# Communication-Shield.net
KiCad netlist of a schematic drawn in Altium Designer
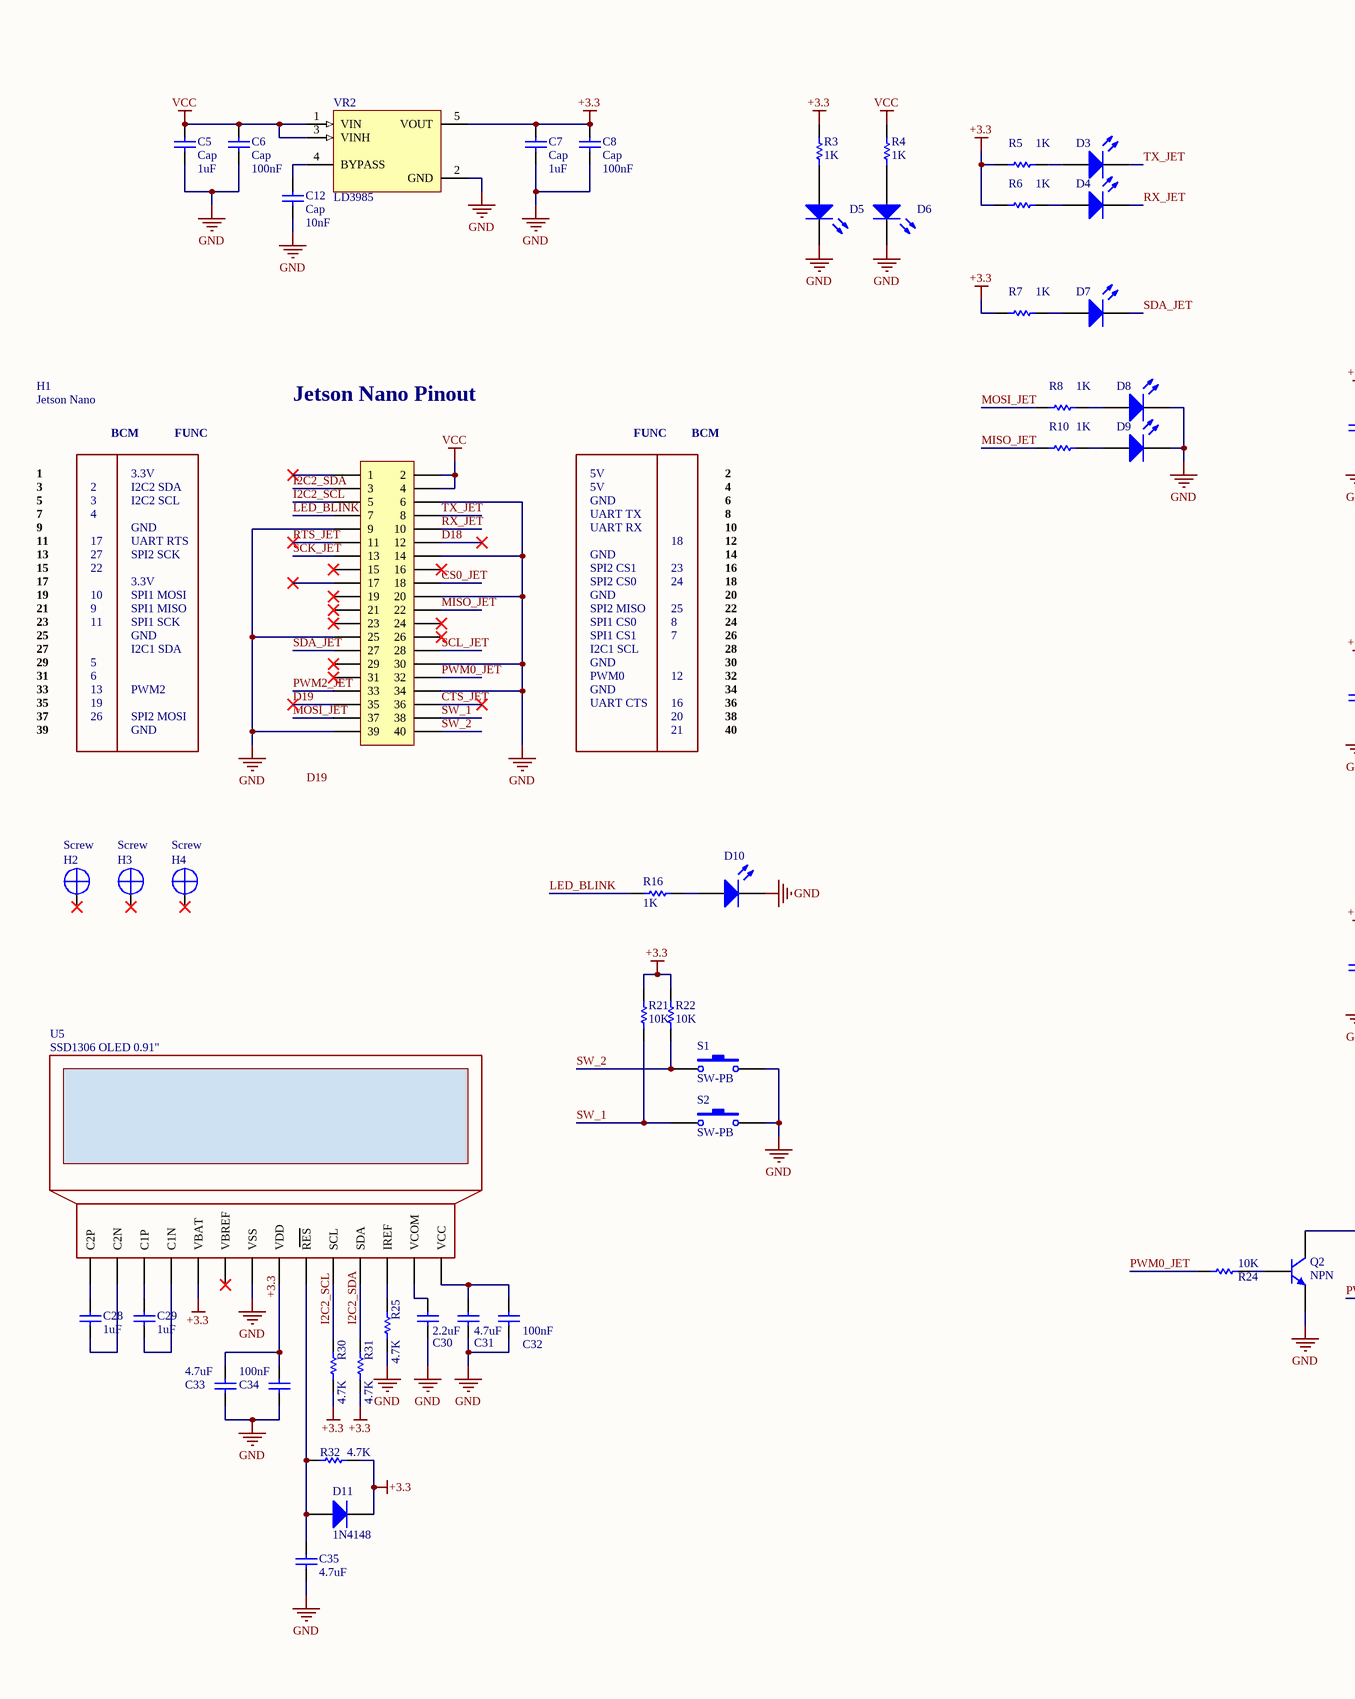
[diagram p0: Communication-Shield.SchDoc, left]
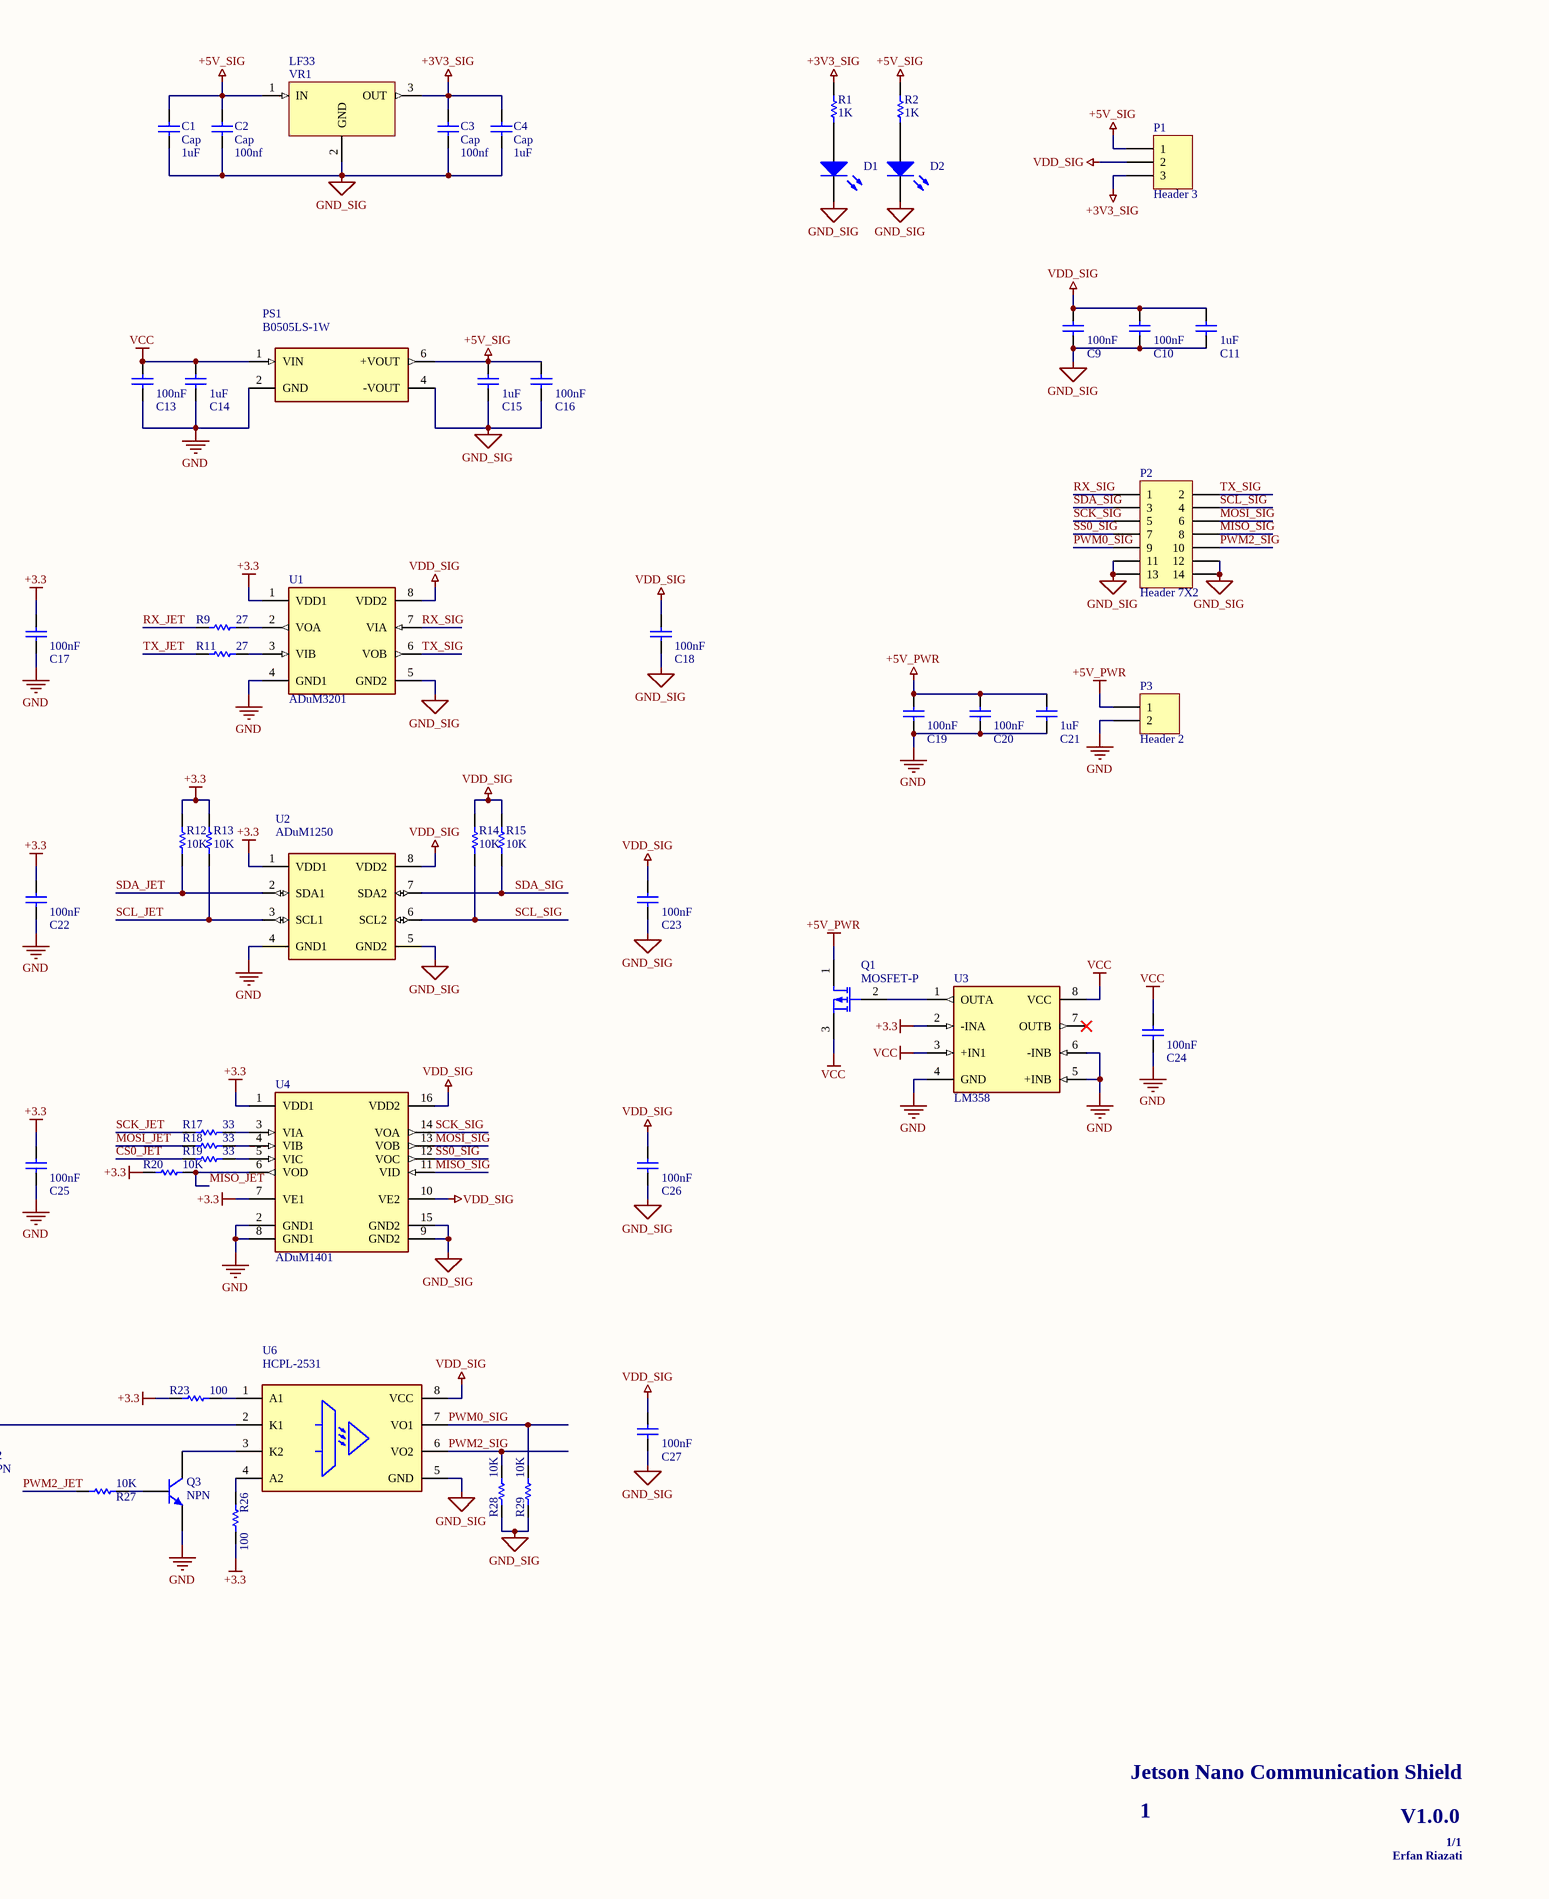
[diagram p1: Communication-Shield.SchDoc, right]

(export (version "E")
  (design (tool "Eeschema 10.0.6"))
  (components
    (comp (ref "C1")
      (value "Cap")
      (footprint "vertigo:C0603")
      (description "Capacitor")
      (fields (field (name "ALTIUM_VALUE") "1uF"))
      (libsource (lib "Miscellaneous Devices") (part "Cap"))
    )
    (comp (ref "C2")
      (value "Cap")
      (footprint "vertigo:C0603")
      (description "Capacitor")
      (fields (field (name "ALTIUM_VALUE") "100nf"))
      (libsource (lib "Miscellaneous Devices") (part "Cap"))
    )
    (comp (ref "C3")
      (value "Cap")
      (footprint "vertigo:C0603")
      (description "Capacitor")
      (fields (field (name "ALTIUM_VALUE") "100nf"))
      (libsource (lib "Miscellaneous Devices") (part "Cap"))
    )
    (comp (ref "C4")
      (value "Cap")
      (footprint "vertigo:C0603")
      (description "Capacitor")
      (fields (field (name "ALTIUM_VALUE") "1uF"))
      (libsource (lib "Miscellaneous Devices") (part "Cap"))
    )
    (comp (ref "C5")
      (value "Cap")
      (footprint "vertigo:C0603")
      (description "Capacitor")
      (fields (field (name "ALTIUM_VALUE") "1uF"))
      (libsource (lib "Miscellaneous Devices") (part "Cap"))
    )
    (comp (ref "C6")
      (value "Cap")
      (footprint "vertigo:C0603")
      (description "Capacitor")
      (fields (field (name "ALTIUM_VALUE") "100nF"))
      (libsource (lib "Miscellaneous Devices") (part "Cap"))
    )
    (comp (ref "C7")
      (value "Cap")
      (footprint "vertigo:C0603")
      (description "Capacitor")
      (fields (field (name "ALTIUM_VALUE") "1uF"))
      (libsource (lib "Miscellaneous Devices") (part "Cap"))
    )
    (comp (ref "C8")
      (value "Cap")
      (footprint "vertigo:C0603")
      (description "Capacitor")
      (fields (field (name "ALTIUM_VALUE") "100nF"))
      (libsource (lib "Miscellaneous Devices") (part "Cap"))
    )
    (comp (ref "C9")
      (value "100nF")
      (footprint "vertigo:C0603")
      (description "Capacitor")
      (fields (field (name "Comment") "Cap"))
      (libsource (lib "Miscellaneous Devices") (part "Cap"))
    )
    (comp (ref "C10")
      (value "100nF")
      (footprint "vertigo:C0603")
      (description "Capacitor")
      (fields (field (name "Comment") "Cap"))
      (libsource (lib "Miscellaneous Devices") (part "Cap"))
    )
    (comp (ref "C11")
      (value "1uF")
      (footprint "vertigo:C0603")
      (description "Capacitor")
      (fields (field (name "Comment") "Cap"))
      (libsource (lib "Miscellaneous Devices") (part "Cap"))
    )
    (comp (ref "C12")
      (value "Cap")
      (footprint "vertigo:C0603")
      (description "Capacitor")
      (fields (field (name "ALTIUM_VALUE") "10nF"))
      (libsource (lib "Miscellaneous Devices") (part "Cap"))
    )
    (comp (ref "C13")
      (value "100nF")
      (footprint "vertigo:C0603")
      (description "Capacitor")
      (fields (field (name "Comment") "Cap"))
      (libsource (lib "Miscellaneous Devices") (part "Cap"))
    )
    (comp (ref "C14")
      (value "1uF")
      (footprint "vertigo:C0603")
      (description "Capacitor")
      (fields (field (name "Comment") "Cap"))
      (libsource (lib "Miscellaneous Devices") (part "Cap"))
    )
    (comp (ref "C15")
      (value "1uF")
      (footprint "vertigo:C0603")
      (description "Capacitor")
      (fields (field (name "Comment") "Cap"))
      (libsource (lib "Miscellaneous Devices") (part "Cap"))
    )
    (comp (ref "C16")
      (value "100nF")
      (footprint "vertigo:C0603")
      (description "Capacitor")
      (fields (field (name "Comment") "Cap"))
      (libsource (lib "Miscellaneous Devices") (part "Cap"))
    )
    (comp (ref "C17")
      (value "100nF")
      (footprint "vertigo:C0603")
      (description "Capacitor")
      (fields (field (name "Comment") "Cap"))
      (libsource (lib "Miscellaneous Devices") (part "Cap"))
    )
    (comp (ref "C18")
      (value "100nF")
      (footprint "vertigo:C0603")
      (description "Capacitor")
      (fields (field (name "Comment") "Cap"))
      (libsource (lib "Miscellaneous Devices") (part "Cap"))
    )
    (comp (ref "C19")
      (value "100nF")
      (footprint "vertigo:C0603")
      (description "Capacitor")
      (fields (field (name "Comment") "Cap"))
      (libsource (lib "Miscellaneous Devices") (part "Cap"))
    )
    (comp (ref "C20")
      (value "100nF")
      (footprint "vertigo:C0603")
      (description "Capacitor")
      (fields (field (name "Comment") "Cap"))
      (libsource (lib "Miscellaneous Devices") (part "Cap"))
    )
    (comp (ref "C21")
      (value "1uF")
      (footprint "vertigo:C0603")
      (description "Capacitor")
      (fields (field (name "Comment") "Cap"))
      (libsource (lib "Miscellaneous Devices") (part "Cap"))
    )
    (comp (ref "C22")
      (value "100nF")
      (footprint "vertigo:C0603")
      (description "Capacitor")
      (fields (field (name "Comment") "Cap"))
      (libsource (lib "Miscellaneous Devices") (part "Cap"))
    )
    (comp (ref "C23")
      (value "100nF")
      (footprint "vertigo:C0603")
      (description "Capacitor")
      (fields (field (name "Comment") "Cap"))
      (libsource (lib "Miscellaneous Devices") (part "Cap"))
    )
    (comp (ref "C24")
      (value "100nF")
      (footprint "vertigo:C0603")
      (description "Capacitor")
      (fields (field (name "Comment") "Cap"))
      (libsource (lib "Miscellaneous Devices") (part "Cap"))
    )
    (comp (ref "C25")
      (value "100nF")
      (footprint "vertigo:C0603")
      (description "Capacitor")
      (fields (field (name "Comment") "Cap"))
      (libsource (lib "Miscellaneous Devices") (part "Cap"))
    )
    (comp (ref "C26")
      (value "100nF")
      (footprint "vertigo:C0603")
      (description "Capacitor")
      (fields (field (name "Comment") "Cap"))
      (libsource (lib "Miscellaneous Devices") (part "Cap"))
    )
    (comp (ref "C27")
      (value "100nF")
      (footprint "vertigo:C0603")
      (description "Capacitor")
      (fields (field (name "Comment") "Cap"))
      (libsource (lib "Miscellaneous Devices") (part "Cap"))
    )
    (comp (ref "C28")
      (value "1uF")
      (footprint "vertigo:C0603")
      (description "Capacitor")
      (fields (field (name "Comment") "Cap"))
      (libsource (lib "Miscellaneous Devices") (part "Cap"))
    )
    (comp (ref "C29")
      (value "1uF")
      (footprint "vertigo:C0603")
      (description "Capacitor")
      (fields (field (name "Comment") "Cap"))
      (libsource (lib "Miscellaneous Devices") (part "Cap"))
    )
    (comp (ref "C30")
      (value "2.2uF")
      (footprint "vertigo:C0603")
      (description "Capacitor")
      (fields (field (name "Comment") "Cap"))
      (libsource (lib "Miscellaneous Devices") (part "Cap"))
    )
    (comp (ref "C31")
      (value "4.7uF")
      (footprint "vertigo:C0603")
      (description "Capacitor")
      (fields (field (name "Comment") "Cap"))
      (libsource (lib "Miscellaneous Devices") (part "Cap"))
    )
    (comp (ref "C32")
      (value "100nF")
      (footprint "vertigo:C0603")
      (description "Capacitor")
      (fields (field (name "Comment") "Cap"))
      (libsource (lib "Miscellaneous Devices") (part "Cap"))
    )
    (comp (ref "C33")
      (value "4.7uF")
      (footprint "vertigo:C0603")
      (description "Capacitor")
      (fields (field (name "Comment") "Cap"))
      (libsource (lib "Miscellaneous Devices") (part "Cap"))
    )
    (comp (ref "C34")
      (value "100nF")
      (footprint "vertigo:C0603")
      (description "Capacitor")
      (fields (field (name "Comment") "Cap"))
      (libsource (lib "Miscellaneous Devices") (part "Cap"))
    )
    (comp (ref "C35")
      (value "4.7uF")
      (footprint "vertigo:C0603")
      (description "Capacitor")
      (fields (field (name "Comment") "Cap"))
      (libsource (lib "Miscellaneous Devices") (part "Cap"))
    )
    (comp (ref "D1")
      (value "Orange")
      (footprint "vertigo:LED-0805 Green")
      (description "Typical RED, GREEN, YELLOW, AMBER GaAs LED")
      (libsource (lib "Miscellaneous Devices") (part "LED2"))
    )
    (comp (ref "D2")
      (value "Orange")
      (footprint "vertigo:LED-0805 Green")
      (description "Typical RED, GREEN, YELLOW, AMBER GaAs LED")
      (libsource (lib "Miscellaneous Devices") (part "LED2"))
    )
    (comp (ref "D3")
      (value "Orange")
      (footprint "vertigo:LED-0805 Orange")
      (description "Typical RED, GREEN, YELLOW, AMBER GaAs LED")
      (libsource (lib "Miscellaneous Devices") (part "LED2"))
    )
    (comp (ref "D4")
      (value "Orange")
      (footprint "vertigo:LED-0805 Orange")
      (description "Typical RED, GREEN, YELLOW, AMBER GaAs LED")
      (libsource (lib "Miscellaneous Devices") (part "LED2"))
    )
    (comp (ref "D5")
      (value "Orange")
      (footprint "vertigo:LED-0805 Green")
      (description "Typical RED, GREEN, YELLOW, AMBER GaAs LED")
      (libsource (lib "Miscellaneous Devices") (part "LED2"))
    )
    (comp (ref "D6")
      (value "Orange")
      (footprint "vertigo:LED-0805 Green")
      (description "Typical RED, GREEN, YELLOW, AMBER GaAs LED")
      (libsource (lib "Miscellaneous Devices") (part "LED2"))
    )
    (comp (ref "D7")
      (value "Orange")
      (footprint "vertigo:LED-0805 Orange")
      (description "Typical RED, GREEN, YELLOW, AMBER GaAs LED")
      (libsource (lib "Miscellaneous Devices") (part "LED2"))
    )
    (comp (ref "D8")
      (value "Orange")
      (footprint "vertigo:LED-0805 Orange")
      (description "Typical RED, GREEN, YELLOW, AMBER GaAs LED")
      (libsource (lib "Miscellaneous Devices") (part "LED2"))
    )
    (comp (ref "D9")
      (value "Orange")
      (footprint "vertigo:LED-0805 Orange")
      (description "Typical RED, GREEN, YELLOW, AMBER GaAs LED")
      (libsource (lib "Miscellaneous Devices") (part "LED2"))
    )
    (comp (ref "D10")
      (value "Orange")
      (footprint "vertigo:LED-0805 Orange")
      (description "Typical RED, GREEN, YELLOW, AMBER GaAs LED")
      (libsource (lib "Miscellaneous Devices") (part "LED2"))
    )
    (comp (ref "D11")
      (value "1N4148")
      (footprint "vertigo:SOD-323 Diode")
      (description "Default Diode")
      (libsource (lib "Miscellaneous Devices") (part "Diode"))
    )
    (comp (ref "H1")
      (value "Jetson Nano")
      (footprint "vertigo:Jetson Nano Header 40-Pin")
      (libsource (lib "vertigo") (part "Jetson Nano"))
    )
    (comp (ref "H2")
      (value "Screw")
      (footprint "vertigo:3mm Screw Hole - 2")
      (description "PCB MOUNTING SCREW")
      (libsource (lib "vertigo") (part "Screw"))
    )
    (comp (ref "H3")
      (value "Screw")
      (footprint "vertigo:3mm Screw Hole - 2")
      (description "PCB MOUNTING SCREW")
      (libsource (lib "vertigo") (part "Screw"))
    )
    (comp (ref "H4")
      (value "Screw")
      (footprint "vertigo:3mm Screw Hole - 2")
      (description "PCB MOUNTING SCREW")
      (libsource (lib "vertigo") (part "Screw"))
    )
    (comp (ref "P1")
      (value "Header 3")
      (footprint "vertigo:Jumper Selector")
      (description "Header, 3-Pin")
      (libsource (lib "Miscellaneous Connectors") (part "Header 3"))
    )
    (comp (ref "P2")
      (value "Header 7X2")
      (footprint "vertigo:IDC 14-Pin 2x7")
      (description "Header, 7-Pin, Dual row")
      (libsource (lib "Miscellaneous Connectors") (part "Header 7X2"))
    )
    (comp (ref "P3")
      (value "Header 2")
      (footprint "vertigo:XH Connector 2-Pin")
      (description "Header, 2-Pin")
      (libsource (lib "Miscellaneous Connectors") (part "Header 2"))
    )
    (comp (ref "PS1")
      (value "B0505LS-1W")
      (footprint "vertigo:B0505LS-1W")
      (description "Compact, isolated DC-DC Converter module")
      (libsource (lib "vertigo") (part "B0505LS-1W"))
    )
    (comp (ref "Q1")
      (value "MOSFET-P")
      (footprint "vertigo:SOT-23")
      (description "P-Channel MOSFET")
      (libsource (lib "Miscellaneous Devices") (part "MOSFET-P"))
    )
    (comp (ref "Q2")
      (value "NPN")
      (footprint "vertigo:SOT-23")
      (description "NPN Bipolar Transistor")
      (libsource (lib "Miscellaneous Devices") (part "NPN"))
    )
    (comp (ref "Q3")
      (value "NPN")
      (footprint "vertigo:SOT-23")
      (description "NPN Bipolar Transistor")
      (libsource (lib "Miscellaneous Devices") (part "NPN"))
    )
    (comp (ref "R1")
      (value "1K")
      (footprint "vertigo:R0603")
      (description "Resistor")
      (fields (field (name "Comment") "Res1"))
      (libsource (lib "Miscellaneous Devices") (part "Res1"))
    )
    (comp (ref "R2")
      (value "1K")
      (footprint "vertigo:R0603")
      (description "Resistor")
      (fields (field (name "Comment") "Res1"))
      (libsource (lib "Miscellaneous Devices") (part "Res1"))
    )
    (comp (ref "R3")
      (value "1K")
      (footprint "vertigo:R0603")
      (description "Resistor")
      (fields (field (name "Comment") "Res1"))
      (libsource (lib "Miscellaneous Devices") (part "Res1"))
    )
    (comp (ref "R4")
      (value "1K")
      (footprint "vertigo:R0603")
      (description "Resistor")
      (fields (field (name "Comment") "Res1"))
      (libsource (lib "Miscellaneous Devices") (part "Res1"))
    )
    (comp (ref "R5")
      (value "1K")
      (footprint "vertigo:R0603")
      (description "Resistor")
      (fields (field (name "Comment") "Res1"))
      (libsource (lib "Miscellaneous Devices") (part "Res1"))
    )
    (comp (ref "R6")
      (value "1K")
      (footprint "vertigo:R0603")
      (description "Resistor")
      (fields (field (name "Comment") "Res1"))
      (libsource (lib "Miscellaneous Devices") (part "Res1"))
    )
    (comp (ref "R7")
      (value "1K")
      (footprint "vertigo:R0603")
      (description "Resistor")
      (fields (field (name "Comment") "Res1"))
      (libsource (lib "Miscellaneous Devices") (part "Res1"))
    )
    (comp (ref "R8")
      (value "1K")
      (footprint "vertigo:R0603")
      (description "Resistor")
      (fields (field (name "Comment") "Res1"))
      (libsource (lib "Miscellaneous Devices") (part "Res1"))
    )
    (comp (ref "R9")
      (value "27")
      (footprint "vertigo:R0603")
      (description "Resistor")
      (fields (field (name "Comment") "Res1"))
      (libsource (lib "Miscellaneous Devices") (part "Res1"))
    )
    (comp (ref "R10")
      (value "1K")
      (footprint "vertigo:R0603")
      (description "Resistor")
      (fields (field (name "Comment") "Res1"))
      (libsource (lib "Miscellaneous Devices") (part "Res1"))
    )
    (comp (ref "R11")
      (value "27")
      (footprint "vertigo:R0603")
      (description "Resistor")
      (fields (field (name "Comment") "Res1"))
      (libsource (lib "Miscellaneous Devices") (part "Res1"))
    )
    (comp (ref "R12")
      (value "10K")
      (footprint "vertigo:R0603")
      (description "Resistor")
      (fields (field (name "Comment") "Res1"))
      (libsource (lib "Miscellaneous Devices") (part "Res1"))
    )
    (comp (ref "R13")
      (value "10K")
      (footprint "vertigo:R0603")
      (description "Resistor")
      (fields (field (name "Comment") "Res1"))
      (libsource (lib "Miscellaneous Devices") (part "Res1"))
    )
    (comp (ref "R14")
      (value "10K")
      (footprint "vertigo:R0603")
      (description "Resistor")
      (fields (field (name "Comment") "Res1"))
      (libsource (lib "Miscellaneous Devices") (part "Res1"))
    )
    (comp (ref "R15")
      (value "10K")
      (footprint "vertigo:R0603")
      (description "Resistor")
      (fields (field (name "Comment") "Res1"))
      (libsource (lib "Miscellaneous Devices") (part "Res1"))
    )
    (comp (ref "R16")
      (value "1K")
      (footprint "vertigo:R0603")
      (description "Resistor")
      (fields (field (name "Comment") "Res1"))
      (libsource (lib "Miscellaneous Devices") (part "Res1"))
    )
    (comp (ref "R17")
      (value "33")
      (footprint "vertigo:R0603")
      (description "Resistor")
      (fields (field (name "Comment") "Res1"))
      (libsource (lib "Miscellaneous Devices") (part "Res1"))
    )
    (comp (ref "R18")
      (value "33")
      (footprint "vertigo:R0603")
      (description "Resistor")
      (fields (field (name "Comment") "Res1"))
      (libsource (lib "Miscellaneous Devices") (part "Res1"))
    )
    (comp (ref "R19")
      (value "33")
      (footprint "vertigo:R0603")
      (description "Resistor")
      (fields (field (name "Comment") "Res1"))
      (libsource (lib "Miscellaneous Devices") (part "Res1"))
    )
    (comp (ref "R20")
      (value "10K")
      (footprint "vertigo:R0603")
      (description "Resistor")
      (fields (field (name "Comment") "Res1"))
      (libsource (lib "Miscellaneous Devices") (part "Res1"))
    )
    (comp (ref "R21")
      (value "10K")
      (footprint "vertigo:R0603")
      (description "Resistor")
      (fields (field (name "Comment") "Res1"))
      (libsource (lib "Miscellaneous Devices") (part "Res1"))
    )
    (comp (ref "R22")
      (value "10K")
      (footprint "vertigo:R0603")
      (description "Resistor")
      (fields (field (name "Comment") "Res1"))
      (libsource (lib "Miscellaneous Devices") (part "Res1"))
    )
    (comp (ref "R23")
      (value "100")
      (footprint "vertigo:R0603")
      (description "Resistor")
      (fields (field (name "Comment") "Res1"))
      (libsource (lib "Miscellaneous Devices") (part "Res1"))
    )
    (comp (ref "R24")
      (value "10K")
      (footprint "vertigo:R0603")
      (description "Resistor")
      (fields (field (name "Comment") "Res1"))
      (libsource (lib "Miscellaneous Devices") (part "Res1"))
    )
    (comp (ref "R25")
      (value "4.7K")
      (footprint "vertigo:R0603")
      (description "Resistor")
      (fields (field (name "Comment") "Res1"))
      (libsource (lib "Miscellaneous Devices") (part "Res1"))
    )
    (comp (ref "R26")
      (value "100")
      (footprint "vertigo:R0603")
      (description "Resistor")
      (fields (field (name "Comment") "Res1"))
      (libsource (lib "Miscellaneous Devices") (part "Res1"))
    )
    (comp (ref "R27")
      (value "10K")
      (footprint "vertigo:R0603")
      (description "Resistor")
      (fields (field (name "Comment") "Res1"))
      (libsource (lib "Miscellaneous Devices") (part "Res1"))
    )
    (comp (ref "R28")
      (value "10K")
      (footprint "vertigo:R0603")
      (description "Resistor")
      (fields (field (name "Comment") "Res1"))
      (libsource (lib "Miscellaneous Devices") (part "Res1"))
    )
    (comp (ref "R29")
      (value "10K")
      (footprint "vertigo:R0603")
      (description "Resistor")
      (fields (field (name "Comment") "Res1"))
      (libsource (lib "Miscellaneous Devices") (part "Res1"))
    )
    (comp (ref "R30")
      (value "4.7K")
      (footprint "vertigo:R0603")
      (description "Resistor")
      (fields (field (name "Comment") "Res1"))
      (libsource (lib "Miscellaneous Devices") (part "Res1"))
    )
    (comp (ref "R31")
      (value "4.7K")
      (footprint "vertigo:R0603")
      (description "Resistor")
      (fields (field (name "Comment") "Res1"))
      (libsource (lib "Miscellaneous Devices") (part "Res1"))
    )
    (comp (ref "R32")
      (value "4.7K")
      (footprint "vertigo:R0603")
      (description "Resistor")
      (fields (field (name "Comment") "Res1"))
      (libsource (lib "Miscellaneous Devices") (part "Res1"))
    )
    (comp (ref "S1")
      (value "SW-PB")
      (footprint "vertigo:Tactile Switch SMD - 2")
      (description "Switch")
      (libsource (lib "Miscellaneous Devices") (part "SW-PB"))
    )
    (comp (ref "S2")
      (value "SW-PB")
      (footprint "vertigo:Tactile Switch SMD - 2")
      (description "Switch")
      (libsource (lib "Miscellaneous Devices") (part "SW-PB"))
    )
    (comp (ref "U1")
      (value "ADuM3201")
      (footprint "vertigo:SOIC-8")
      (description "Dual-Channel, Digital Isolators, Enhanced System-Level ESD Reliability")
      (libsource (lib "vertigo") (part "ADuM3201"))
    )
    (comp (ref "U2")
      (value "ADuM1250")
      (footprint "vertigo:SOIC-8")
      (description "Hot Swappable, Dual I2C Isolators")
      (libsource (lib "vertigo") (part "ADuM1250"))
    )
    (comp (ref "U3")
      (value "LM358")
      (footprint "vertigo:SOIC-8")
      (description "2-Channel, 1MHz, industry standard, 32V Op-Amp")
      (libsource (lib "vertigo") (part "LM358"))
    )
    (comp (ref "U4")
      (value "ADuM1401")
      (footprint "vertigo:SOIC-16")
      (description "Quad-Channel Digital Isolators")
      (libsource (lib "vertigo") (part "ADuM1401"))
    )
    (comp (ref "U5")
      (value "SSD1306 OLED 0.91\"")
      (footprint "vertigo:SSD1306 OLED 0.91\"")
      (libsource (lib "vertigo") (part "SSD1306 OLED 0.91{dblquote}"))
    )
    (comp (ref "U6")
      (value "HCPL-2531")
      (footprint "vertigo:SOIC-8")
      (libsource (lib "vertigo") (part "HCPL-2531"))
    )
    (comp (ref "VR1")
      (value "LF33")
      (footprint "DPAK TO-252")
      (description "Very low drop voltage regulator with inhibit function")
      (libsource (lib "vertigo") (part "LF33"))
    )
    (comp (ref "VR2")
      (value "LD3985")
      (footprint "SOT23-5")
      (description "Ultra low drop and low noise BiCMOS voltage regulators")
      (libsource (lib "vertigo") (part "LD3985"))
    )
  )
  (nets
    (net (code "1") (name "+3.3") (class "Default")
      (node (ref "C17") (pin "1") (pinfunction "1_1") (pintype "passive"))
      (node (ref "C22") (pin "1") (pinfunction "1_1") (pintype "passive"))
      (node (ref "C25") (pin "1") (pinfunction "1_1") (pintype "passive"))
      (node (ref "C33") (pin "1") (pinfunction "1_1") (pintype "passive"))
      (node (ref "C34") (pin "1") (pinfunction "1_1") (pintype "passive"))
      (node (ref "C7") (pin "2") (pinfunction "2_2") (pintype "passive"))
      (node (ref "C8") (pin "2") (pinfunction "2_2") (pintype "passive"))
      (node (ref "D11") (pin "2") (pinfunction "K_2") (pintype "passive"))
      (node (ref "R12") (pin "2") (pinfunction "2_2") (pintype "passive"))
      (node (ref "R13") (pin "2") (pinfunction "2_2") (pintype "passive"))
      (node (ref "R20") (pin "1") (pinfunction "1_1") (pintype "passive"))
      (node (ref "R21") (pin "2") (pinfunction "2_2") (pintype "passive"))
      (node (ref "R22") (pin "2") (pinfunction "2_2") (pintype "passive"))
      (node (ref "R23") (pin "2") (pinfunction "2_2") (pintype "passive"))
      (node (ref "R26") (pin "1") (pinfunction "1_1") (pintype "passive"))
      (node (ref "R3") (pin "1") (pinfunction "1_1") (pintype "passive"))
      (node (ref "R30") (pin "1") (pinfunction "1_1") (pintype "passive"))
      (node (ref "R31") (pin "1") (pinfunction "1_1") (pintype "passive"))
      (node (ref "R32") (pin "1") (pinfunction "1_1") (pintype "passive"))
      (node (ref "R5") (pin "1") (pinfunction "1_1") (pintype "passive"))
      (node (ref "R6") (pin "1") (pinfunction "1_1") (pintype "passive"))
      (node (ref "R7") (pin "1") (pinfunction "1_1") (pintype "passive"))
      (node (ref "U1") (pin "1") (pinfunction "VDD1_1") (pintype "power_in"))
      (node (ref "U2") (pin "1") (pinfunction "VDD1_1") (pintype "power_in"))
      (node (ref "U3") (pin "2") (pinfunction "-INA_2") (pintype "input"))
      (node (ref "U4") (pin "1") (pinfunction "VDD1_1") (pintype "power_in"))
      (node (ref "U4") (pin "7") (pinfunction "VE1_7") (pintype "passive"))
      (node (ref "U5") (pin "5") (pinfunction "VBAT_5") (pintype "passive"))
      (node (ref "U5") (pin "8") (pinfunction "VDD_8") (pintype "passive"))
      (node (ref "VR2") (pin "5") (pinfunction "VOUT_5") (pintype "power_in"))
    )
    (net (code "2") (name "+3V3_SIG") (class "Default")
      (node (ref "C3") (pin "2") (pinfunction "2_2") (pintype "passive"))
      (node (ref "C4") (pin "2") (pinfunction "2_2") (pintype "passive"))
      (node (ref "P1") (pin "3") (pinfunction "3_3") (pintype "passive"))
      (node (ref "R1") (pin "1") (pinfunction "1_1") (pintype "passive"))
      (node (ref "VR1") (pin "3") (pinfunction "OUT_3") (pintype "output"))
    )
    (net (code "3") (name "+5V_PWR") (class "Default")
      (node (ref "C19") (pin "1") (pinfunction "1_1") (pintype "passive"))
      (node (ref "C20") (pin "1") (pinfunction "1_1") (pintype "passive"))
      (node (ref "C21") (pin "1") (pinfunction "1_1") (pintype "passive"))
      (node (ref "P3") (pin "1") (pinfunction "1_1") (pintype "passive"))
      (node (ref "Q1") (pin "1") (pinfunction "D_1") (pintype "passive"))
    )
    (net (code "4") (name "+5V_SIG") (class "Default")
      (node (ref "C1") (pin "2") (pinfunction "2_2") (pintype "passive"))
      (node (ref "C15") (pin "1") (pinfunction "1_1") (pintype "passive"))
      (node (ref "C16") (pin "1") (pinfunction "1_1") (pintype "passive"))
      (node (ref "C2") (pin "2") (pinfunction "2_2") (pintype "passive"))
      (node (ref "P1") (pin "1") (pinfunction "1_1") (pintype "passive"))
      (node (ref "PS1") (pin "6") (pinfunction "+VOUT_6") (pintype "output"))
      (node (ref "R2") (pin "1") (pinfunction "1_1") (pintype "passive"))
      (node (ref "VR1") (pin "1") (pinfunction "IN_1") (pintype "input"))
    )
    (net (code "5") (name "/CS0_JET") (class "Default")
      (node (ref "H1") (pin "18") (pinfunction "18_18") (pintype "passive"))
      (node (ref "R19") (pin "2") (pinfunction "2_2") (pintype "passive"))
    )
    (net (code "6") (name "/CTS_JET") (class "Default")
      (node (ref "H1") (pin "36") (pinfunction "36_36") (pintype "passive+no_connect"))
    )
    (net (code "7") (name "/D18") (class "Default")
      (node (ref "H1") (pin "12") (pinfunction "12_12") (pintype "passive+no_connect"))
    )
    (net (code "8") (name "/D19") (class "Default")
      (node (ref "H1") (pin "35") (pinfunction "35_35") (pintype "passive"))
    )
    (net (code "9") (name "/I2C2_SCL") (class "Default")
      (node (ref "H1") (pin "5") (pinfunction "5_5") (pintype "passive"))
      (node (ref "R30") (pin "2") (pinfunction "2_2") (pintype "passive"))
      (node (ref "U5") (pin "10") (pinfunction "SCL_10") (pintype "passive"))
    )
    (net (code "10") (name "/I2C2_SDA") (class "Default")
      (node (ref "H1") (pin "3") (pinfunction "3_3") (pintype "passive"))
      (node (ref "R31") (pin "2") (pinfunction "2_2") (pintype "passive"))
      (node (ref "U5") (pin "11") (pinfunction "SDA_11") (pintype "passive"))
    )
    (net (code "11") (name "/LED_BLINK") (class "Default")
      (node (ref "H1") (pin "7") (pinfunction "7_7") (pintype "passive"))
      (node (ref "R16") (pin "1") (pinfunction "1_1") (pintype "passive"))
    )
    (net (code "12") (name "/MISO_JET") (class "Default")
      (node (ref "H1") (pin "22") (pinfunction "22_22") (pintype "passive"))
      (node (ref "R10") (pin "1") (pinfunction "1_1") (pintype "passive"))
      (node (ref "R20") (pin "2") (pinfunction "2_2") (pintype "passive"))
      (node (ref "U4") (pin "6") (pinfunction "VOD_6") (pintype "output"))
    )
    (net (code "13") (name "/MISO_SIG") (class "Default")
      (node (ref "P2") (pin "8") (pinfunction "8_8") (pintype "passive"))
      (node (ref "U4") (pin "11") (pinfunction "VID_11") (pintype "input"))
    )
    (net (code "14") (name "/MOSI_JET") (class "Default")
      (node (ref "H1") (pin "37") (pinfunction "37_37") (pintype "passive"))
      (node (ref "R18") (pin "2") (pinfunction "2_2") (pintype "passive"))
      (node (ref "R8") (pin "1") (pinfunction "1_1") (pintype "passive"))
    )
    (net (code "15") (name "/MOSI_SIG") (class "Default")
      (node (ref "P2") (pin "6") (pinfunction "6_6") (pintype "passive"))
      (node (ref "U4") (pin "13") (pinfunction "VOB_13") (pintype "output"))
    )
    (net (code "16") (name "/PWM0_JET") (class "Default")
      (node (ref "H1") (pin "32") (pinfunction "32_32") (pintype "passive"))
      (node (ref "R24") (pin "2") (pinfunction "2_2") (pintype "passive"))
    )
    (net (code "17") (name "/PWM0_SIG") (class "Default")
      (node (ref "P2") (pin "9") (pinfunction "9_9") (pintype "passive"))
      (node (ref "R29") (pin "1") (pinfunction "1_1") (pintype "passive"))
      (node (ref "U6") (pin "7") (pinfunction "VO1_7") (pintype "power_in"))
    )
    (net (code "18") (name "/PWM2_JET") (class "Default")
      (node (ref "H1") (pin "33") (pinfunction "33_33") (pintype "passive"))
      (node (ref "R27") (pin "2") (pinfunction "2_2") (pintype "passive"))
    )
    (net (code "19") (name "/PWM2_SIG") (class "Default")
      (node (ref "P2") (pin "10") (pinfunction "10_10") (pintype "passive"))
      (node (ref "R28") (pin "1") (pinfunction "1_1") (pintype "passive"))
      (node (ref "U6") (pin "6") (pinfunction "VO2_6") (pintype "power_in"))
    )
    (net (code "20") (name "/RTS_JET") (class "Default")
      (node (ref "H1") (pin "11") (pinfunction "11_11") (pintype "passive+no_connect"))
    )
    (net (code "21") (name "/RX_JET") (class "Default")
      (node (ref "D4") (pin "2") (pinfunction "K_2") (pintype "passive"))
      (node (ref "H1") (pin "10") (pinfunction "10_10") (pintype "passive"))
      (node (ref "R9") (pin "2") (pinfunction "2_2") (pintype "passive"))
    )
    (net (code "22") (name "/RX_SIG") (class "Default")
      (node (ref "P2") (pin "1") (pinfunction "1_1") (pintype "passive"))
      (node (ref "U1") (pin "7") (pinfunction "VIA_7") (pintype "input"))
    )
    (net (code "23") (name "/SCK_JET") (class "Default")
      (node (ref "H1") (pin "13") (pinfunction "13_13") (pintype "passive"))
      (node (ref "R17") (pin "2") (pinfunction "2_2") (pintype "passive"))
    )
    (net (code "24") (name "/SCK_SIG") (class "Default")
      (node (ref "P2") (pin "5") (pinfunction "5_5") (pintype "passive"))
      (node (ref "U4") (pin "14") (pinfunction "VOA_14") (pintype "output"))
    )
    (net (code "25") (name "/SCL_JET") (class "Default")
      (node (ref "H1") (pin "28") (pinfunction "28_28") (pintype "passive"))
      (node (ref "R13") (pin "1") (pinfunction "1_1") (pintype "passive"))
      (node (ref "U2") (pin "3") (pinfunction "SCL1_3") (pintype "bidirectional"))
    )
    (net (code "26") (name "/SCL_SIG") (class "Default")
      (node (ref "P2") (pin "4") (pinfunction "4_4") (pintype "passive"))
      (node (ref "R14") (pin "1") (pinfunction "1_1") (pintype "passive"))
      (node (ref "U2") (pin "6") (pinfunction "SCL2_6") (pintype "bidirectional"))
    )
    (net (code "27") (name "/SDA_JET") (class "Default")
      (node (ref "D7") (pin "2") (pinfunction "K_2") (pintype "passive"))
      (node (ref "H1") (pin "27") (pinfunction "27_27") (pintype "passive"))
      (node (ref "R12") (pin "1") (pinfunction "1_1") (pintype "passive"))
      (node (ref "U2") (pin "2") (pinfunction "SDA1_2") (pintype "bidirectional"))
    )
    (net (code "28") (name "/SDA_SIG") (class "Default")
      (node (ref "P2") (pin "3") (pinfunction "3_3") (pintype "passive"))
      (node (ref "R15") (pin "1") (pinfunction "1_1") (pintype "passive"))
      (node (ref "U2") (pin "7") (pinfunction "SDA2_7") (pintype "bidirectional"))
    )
    (net (code "29") (name "/SS0_SIG") (class "Default")
      (node (ref "P2") (pin "7") (pinfunction "7_7") (pintype "passive"))
      (node (ref "U4") (pin "12") (pinfunction "VOC_12") (pintype "output"))
    )
    (net (code "30") (name "/SW_1") (class "Default")
      (node (ref "H1") (pin "38") (pinfunction "38_38") (pintype "passive"))
      (node (ref "R21") (pin "1") (pinfunction "1_1") (pintype "passive"))
      (node (ref "S2") (pin "1") (pinfunction "1_1") (pintype "passive"))
    )
    (net (code "31") (name "/SW_2") (class "Default")
      (node (ref "H1") (pin "40") (pinfunction "40_40") (pintype "passive"))
      (node (ref "R22") (pin "1") (pinfunction "1_1") (pintype "passive"))
      (node (ref "S1") (pin "1") (pinfunction "1_1") (pintype "passive"))
    )
    (net (code "32") (name "/TX_JET") (class "Default")
      (node (ref "D3") (pin "2") (pinfunction "K_2") (pintype "passive"))
      (node (ref "H1") (pin "8") (pinfunction "8_8") (pintype "passive"))
      (node (ref "R11") (pin "2") (pinfunction "2_2") (pintype "passive"))
    )
    (net (code "33") (name "/TX_SIG") (class "Default")
      (node (ref "P2") (pin "2") (pinfunction "2_2") (pintype "passive"))
      (node (ref "U1") (pin "6") (pinfunction "VOB_6") (pintype "output"))
    )
    (net (code "34") (name "GND") (class "Default")
      (node (ref "C12") (pin "1") (pinfunction "1_1") (pintype "passive"))
      (node (ref "C13") (pin "2") (pinfunction "2_2") (pintype "passive"))
      (node (ref "C14") (pin "2") (pinfunction "2_2") (pintype "passive"))
      (node (ref "C17") (pin "2") (pinfunction "2_2") (pintype "passive"))
      (node (ref "C19") (pin "2") (pinfunction "2_2") (pintype "passive"))
      (node (ref "C20") (pin "2") (pinfunction "2_2") (pintype "passive"))
      (node (ref "C21") (pin "2") (pinfunction "2_2") (pintype "passive"))
      (node (ref "C22") (pin "2") (pinfunction "2_2") (pintype "passive"))
      (node (ref "C24") (pin "2") (pinfunction "2_2") (pintype "passive"))
      (node (ref "C25") (pin "2") (pinfunction "2_2") (pintype "passive"))
      (node (ref "C30") (pin "2") (pinfunction "2_2") (pintype "passive"))
      (node (ref "C31") (pin "2") (pinfunction "2_2") (pintype "passive"))
      (node (ref "C32") (pin "2") (pinfunction "2_2") (pintype "passive"))
      (node (ref "C33") (pin "2") (pinfunction "2_2") (pintype "passive"))
      (node (ref "C34") (pin "2") (pinfunction "2_2") (pintype "passive"))
      (node (ref "C35") (pin "2") (pinfunction "2_2") (pintype "passive"))
      (node (ref "C5") (pin "1") (pinfunction "1_1") (pintype "passive"))
      (node (ref "C6") (pin "1") (pinfunction "1_1") (pintype "passive"))
      (node (ref "C7") (pin "1") (pinfunction "1_1") (pintype "passive"))
      (node (ref "C8") (pin "1") (pinfunction "1_1") (pintype "passive"))
      (node (ref "D10") (pin "2") (pinfunction "K_2") (pintype "passive"))
      (node (ref "D5") (pin "2") (pinfunction "K_2") (pintype "passive"))
      (node (ref "D6") (pin "2") (pinfunction "K_2") (pintype "passive"))
      (node (ref "D8") (pin "2") (pinfunction "K_2") (pintype "passive"))
      (node (ref "D9") (pin "2") (pinfunction "K_2") (pintype "passive"))
      (node (ref "H1") (pin "14") (pinfunction "14_14") (pintype "passive"))
      (node (ref "H1") (pin "20") (pinfunction "20_20") (pintype "passive"))
      (node (ref "H1") (pin "25") (pinfunction "25_25") (pintype "passive"))
      (node (ref "H1") (pin "30") (pinfunction "30_30") (pintype "passive"))
      (node (ref "H1") (pin "34") (pinfunction "34_34") (pintype "passive"))
      (node (ref "H1") (pin "39") (pinfunction "39_39") (pintype "passive"))
      (node (ref "H1") (pin "6") (pinfunction "6_6") (pintype "passive"))
      (node (ref "H1") (pin "9") (pinfunction "9_9") (pintype "passive"))
      (node (ref "P3") (pin "2") (pinfunction "2_2") (pintype "passive"))
      (node (ref "PS1") (pin "2") (pinfunction "GND_2") (pintype "power_in"))
      (node (ref "Q2") (pin "3") (pinfunction "E_3") (pintype "passive"))
      (node (ref "Q3") (pin "3") (pinfunction "E_3") (pintype "passive"))
      (node (ref "R25") (pin "1") (pinfunction "1_1") (pintype "passive"))
      (node (ref "S1") (pin "2") (pinfunction "2_2") (pintype "passive"))
      (node (ref "S2") (pin "2") (pinfunction "2_2") (pintype "passive"))
      (node (ref "U1") (pin "4") (pinfunction "GND1_4") (pintype "power_in"))
      (node (ref "U2") (pin "4") (pinfunction "GND1_4") (pintype "power_in"))
      (node (ref "U3") (pin "4") (pinfunction "GND_4") (pintype "power_in"))
      (node (ref "U3") (pin "5") (pinfunction "+INB_5") (pintype "input"))
      (node (ref "U3") (pin "6") (pinfunction "-INB_6") (pintype "input"))
      (node (ref "U4") (pin "2") (pinfunction "GND1_2") (pintype "power_in"))
      (node (ref "U4") (pin "8") (pinfunction "GND1_8") (pintype "power_in"))
      (node (ref "U5") (pin "7") (pinfunction "VSS_7") (pintype "passive"))
      (node (ref "VR2") (pin "2") (pinfunction "GND_2") (pintype "power_in"))
    )
    (net (code "35") (name "GND_SIG") (class "Default")
      (node (ref "C1") (pin "1") (pinfunction "1_1") (pintype "passive"))
      (node (ref "C10") (pin "2") (pinfunction "2_2") (pintype "passive"))
      (node (ref "C11") (pin "2") (pinfunction "2_2") (pintype "passive"))
      (node (ref "C15") (pin "2") (pinfunction "2_2") (pintype "passive"))
      (node (ref "C16") (pin "2") (pinfunction "2_2") (pintype "passive"))
      (node (ref "C18") (pin "2") (pinfunction "2_2") (pintype "passive"))
      (node (ref "C2") (pin "1") (pinfunction "1_1") (pintype "passive"))
      (node (ref "C23") (pin "2") (pinfunction "2_2") (pintype "passive"))
      (node (ref "C26") (pin "2") (pinfunction "2_2") (pintype "passive"))
      (node (ref "C27") (pin "2") (pinfunction "2_2") (pintype "passive"))
      (node (ref "C3") (pin "1") (pinfunction "1_1") (pintype "passive"))
      (node (ref "C4") (pin "1") (pinfunction "1_1") (pintype "passive"))
      (node (ref "C9") (pin "2") (pinfunction "2_2") (pintype "passive"))
      (node (ref "D1") (pin "2") (pinfunction "K_2") (pintype "passive"))
      (node (ref "D2") (pin "2") (pinfunction "K_2") (pintype "passive"))
      (node (ref "P2") (pin "11") (pinfunction "11_11") (pintype "passive"))
      (node (ref "P2") (pin "12") (pinfunction "12_12") (pintype "passive"))
      (node (ref "P2") (pin "13") (pinfunction "13_13") (pintype "passive"))
      (node (ref "P2") (pin "14") (pinfunction "14_14") (pintype "passive"))
      (node (ref "PS1") (pin "4") (pinfunction "-VOUT_4") (pintype "passive"))
      (node (ref "R28") (pin "2") (pinfunction "2_2") (pintype "passive"))
      (node (ref "R29") (pin "2") (pinfunction "2_2") (pintype "passive"))
      (node (ref "U1") (pin "5") (pinfunction "GND2_5") (pintype "power_in"))
      (node (ref "U2") (pin "5") (pinfunction "GND2_5") (pintype "power_in"))
      (node (ref "U4") (pin "15") (pinfunction "GND2_15") (pintype "power_in"))
      (node (ref "U4") (pin "9") (pinfunction "GND2_9") (pintype "power_in"))
      (node (ref "U6") (pin "5") (pinfunction "GND_5") (pintype "power_in"))
      (node (ref "VR1") (pin "2") (pinfunction "GND_2") (pintype "passive"))
    )
    (net (code "36") (name "Net-(D1-A)") (class "Default")
      (node (ref "D1") (pin "1") (pinfunction "A_1") (pintype "passive"))
      (node (ref "R1") (pin "2") (pinfunction "2_2") (pintype "passive"))
    )
    (net (code "37") (name "Net-(D2-A)") (class "Default")
      (node (ref "D2") (pin "1") (pinfunction "A_1") (pintype "passive"))
      (node (ref "R2") (pin "2") (pinfunction "2_2") (pintype "passive"))
    )
    (net (code "38") (name "Net-(D3-A)") (class "Default")
      (node (ref "D3") (pin "1") (pinfunction "A_1") (pintype "passive"))
      (node (ref "R5") (pin "2") (pinfunction "2_2") (pintype "passive"))
    )
    (net (code "39") (name "Net-(D4-A)") (class "Default")
      (node (ref "D4") (pin "1") (pinfunction "A_1") (pintype "passive"))
      (node (ref "R6") (pin "2") (pinfunction "2_2") (pintype "passive"))
    )
    (net (code "40") (name "Net-(D5-A)") (class "Default")
      (node (ref "D5") (pin "1") (pinfunction "A_1") (pintype "passive"))
      (node (ref "R3") (pin "2") (pinfunction "2_2") (pintype "passive"))
    )
    (net (code "41") (name "Net-(D6-A)") (class "Default")
      (node (ref "D6") (pin "1") (pinfunction "A_1") (pintype "passive"))
      (node (ref "R4") (pin "2") (pinfunction "2_2") (pintype "passive"))
    )
    (net (code "42") (name "Net-(D7-A)") (class "Default")
      (node (ref "D7") (pin "1") (pinfunction "A_1") (pintype "passive"))
      (node (ref "R7") (pin "2") (pinfunction "2_2") (pintype "passive"))
    )
    (net (code "43") (name "Net-(D8-A)") (class "Default")
      (node (ref "D8") (pin "1") (pinfunction "A_1") (pintype "passive"))
      (node (ref "R8") (pin "2") (pinfunction "2_2") (pintype "passive"))
    )
    (net (code "44") (name "Net-(D9-A)") (class "Default")
      (node (ref "D9") (pin "1") (pinfunction "A_1") (pintype "passive"))
      (node (ref "R10") (pin "2") (pinfunction "2_2") (pintype "passive"))
    )
    (net (code "45") (name "Net-(D10-A)") (class "Default")
      (node (ref "D10") (pin "1") (pinfunction "A_1") (pintype "passive"))
      (node (ref "R16") (pin "2") (pinfunction "2_2") (pintype "passive"))
    )
    (net (code "46") (name "Net-(D11-A)") (class "Default")
      (node (ref "C35") (pin "1") (pinfunction "1_1") (pintype "passive"))
      (node (ref "D11") (pin "1") (pinfunction "A_1") (pintype "passive"))
      (node (ref "R32") (pin "2") (pinfunction "2_2") (pintype "passive"))
      (node (ref "U5") (pin "9") (pinfunction "RES_9") (pintype "passive"))
    )
    (net (code "47") (name "Net-(Q1-G)") (class "Default")
      (node (ref "Q1") (pin "2") (pinfunction "G_2") (pintype "passive"))
      (node (ref "U3") (pin "1") (pinfunction "OUTA_1") (pintype "output"))
    )
    (net (code "48") (name "Net-(Q2-B)") (class "Default")
      (node (ref "Q2") (pin "2") (pinfunction "B_2") (pintype "passive"))
      (node (ref "R24") (pin "1") (pinfunction "1_1") (pintype "passive"))
    )
    (net (code "49") (name "Net-(Q2-C)") (class "Default")
      (node (ref "Q2") (pin "1") (pinfunction "C_1") (pintype "passive"))
      (node (ref "U6") (pin "2") (pinfunction "K1_2") (pintype "power_in"))
    )
    (net (code "50") (name "Net-(Q3-B)") (class "Default")
      (node (ref "Q3") (pin "2") (pinfunction "B_2") (pintype "passive"))
      (node (ref "R27") (pin "1") (pinfunction "1_1") (pintype "passive"))
    )
    (net (code "51") (name "Net-(Q3-C)") (class "Default")
      (node (ref "Q3") (pin "1") (pinfunction "C_1") (pintype "passive"))
      (node (ref "U6") (pin "3") (pinfunction "K2_3") (pintype "power_in"))
    )
    (net (code "52") (name "Net-(U1-VIB)") (class "Default")
      (node (ref "R11") (pin "1") (pinfunction "1_1") (pintype "passive"))
      (node (ref "U1") (pin "3") (pinfunction "VIB_3") (pintype "input"))
    )
    (net (code "53") (name "Net-(U1-VOA)") (class "Default")
      (node (ref "R9") (pin "1") (pinfunction "1_1") (pintype "passive"))
      (node (ref "U1") (pin "2") (pinfunction "VOA_2") (pintype "output"))
    )
    (net (code "54") (name "Net-(U4-VIA)") (class "Default")
      (node (ref "R17") (pin "1") (pinfunction "1_1") (pintype "passive"))
      (node (ref "U4") (pin "3") (pinfunction "VIA_3") (pintype "input"))
    )
    (net (code "55") (name "Net-(U4-VIB)") (class "Default")
      (node (ref "R18") (pin "1") (pinfunction "1_1") (pintype "passive"))
      (node (ref "U4") (pin "4") (pinfunction "VIB_4") (pintype "input"))
    )
    (net (code "56") (name "Net-(U4-VIC)") (class "Default")
      (node (ref "R19") (pin "1") (pinfunction "1_1") (pintype "passive"))
      (node (ref "U4") (pin "5") (pinfunction "VIC_5") (pintype "input"))
    )
    (net (code "57") (name "Net-(U5-C1N)") (class "Default")
      (node (ref "C29") (pin "2") (pinfunction "2_2") (pintype "passive"))
      (node (ref "U5") (pin "4") (pinfunction "C1N_4") (pintype "passive"))
    )
    (net (code "58") (name "Net-(U5-C1P)") (class "Default")
      (node (ref "C29") (pin "1") (pinfunction "1_1") (pintype "passive"))
      (node (ref "U5") (pin "3") (pinfunction "C1P_3") (pintype "passive"))
    )
    (net (code "59") (name "Net-(U5-C2N)") (class "Default")
      (node (ref "C28") (pin "2") (pinfunction "2_2") (pintype "passive"))
      (node (ref "U5") (pin "2") (pinfunction "C2N_2") (pintype "passive"))
    )
    (net (code "60") (name "Net-(U5-C2P)") (class "Default")
      (node (ref "C28") (pin "1") (pinfunction "1_1") (pintype "passive"))
      (node (ref "U5") (pin "1") (pinfunction "C2P_1") (pintype "passive"))
    )
    (net (code "61") (name "Net-(U5-IREF)") (class "Default")
      (node (ref "R25") (pin "2") (pinfunction "2_2") (pintype "passive"))
      (node (ref "U5") (pin "12") (pinfunction "IREF_12") (pintype "passive"))
    )
    (net (code "62") (name "Net-(U5-VCC)") (class "Default")
      (node (ref "C31") (pin "1") (pinfunction "1_1") (pintype "passive"))
      (node (ref "C32") (pin "1") (pinfunction "1_1") (pintype "passive"))
      (node (ref "U5") (pin "14") (pinfunction "VCC_14") (pintype "passive"))
    )
    (net (code "63") (name "Net-(U5-VCOM)") (class "Default")
      (node (ref "C30") (pin "1") (pinfunction "1_1") (pintype "passive"))
      (node (ref "U5") (pin "13") (pinfunction "VCOM_13") (pintype "passive"))
    )
    (net (code "64") (name "Net-(U6-A1)") (class "Default")
      (node (ref "R23") (pin "1") (pinfunction "1_1") (pintype "passive"))
      (node (ref "U6") (pin "1") (pinfunction "A1_1") (pintype "power_in"))
    )
    (net (code "65") (name "Net-(U6-A2)") (class "Default")
      (node (ref "R26") (pin "2") (pinfunction "2_2") (pintype "passive"))
      (node (ref "U6") (pin "4") (pinfunction "A2_4") (pintype "power_in"))
    )
    (net (code "66") (name "Net-(VR2-BYPASS)") (class "Default")
      (node (ref "C12") (pin "2") (pinfunction "2_2") (pintype "passive"))
      (node (ref "VR2") (pin "4") (pinfunction "BYPASS_4") (pintype "passive"))
    )
    (net (code "67") (name "VCC") (class "Default")
      (node (ref "C13") (pin "1") (pinfunction "1_1") (pintype "passive"))
      (node (ref "C14") (pin "1") (pinfunction "1_1") (pintype "passive"))
      (node (ref "C24") (pin "1") (pinfunction "1_1") (pintype "passive"))
      (node (ref "C5") (pin "2") (pinfunction "2_2") (pintype "passive"))
      (node (ref "C6") (pin "2") (pinfunction "2_2") (pintype "passive"))
      (node (ref "H1") (pin "2") (pinfunction "2_2") (pintype "passive"))
      (node (ref "H1") (pin "4") (pinfunction "4_4") (pintype "passive"))
      (node (ref "PS1") (pin "1") (pinfunction "VIN_1") (pintype "input"))
      (node (ref "Q1") (pin "3") (pinfunction "S_3") (pintype "passive"))
      (node (ref "R4") (pin "1") (pinfunction "1_1") (pintype "passive"))
      (node (ref "U3") (pin "3") (pinfunction "+IN1_3") (pintype "input"))
      (node (ref "U3") (pin "8") (pinfunction "VCC_8") (pintype "power_in"))
      (node (ref "VR2") (pin "1") (pinfunction "VIN_1") (pintype "input"))
      (node (ref "VR2") (pin "3") (pinfunction "VINH_3") (pintype "input"))
    )
    (net (code "68") (name "VDD_SIG") (class "Default")
      (node (ref "C10") (pin "1") (pinfunction "1_1") (pintype "passive"))
      (node (ref "C11") (pin "1") (pinfunction "1_1") (pintype "passive"))
      (node (ref "C18") (pin "1") (pinfunction "1_1") (pintype "passive"))
      (node (ref "C23") (pin "1") (pinfunction "1_1") (pintype "passive"))
      (node (ref "C26") (pin "1") (pinfunction "1_1") (pintype "passive"))
      (node (ref "C27") (pin "1") (pinfunction "1_1") (pintype "passive"))
      (node (ref "C9") (pin "1") (pinfunction "1_1") (pintype "passive"))
      (node (ref "P1") (pin "2") (pinfunction "2_2") (pintype "passive"))
      (node (ref "R14") (pin "2") (pinfunction "2_2") (pintype "passive"))
      (node (ref "R15") (pin "2") (pinfunction "2_2") (pintype "passive"))
      (node (ref "U1") (pin "8") (pinfunction "VDD2_8") (pintype "power_in"))
      (node (ref "U2") (pin "8") (pinfunction "VDD2_8") (pintype "power_in"))
      (node (ref "U4") (pin "10") (pinfunction "VE2_10") (pintype "passive"))
      (node (ref "U4") (pin "16") (pinfunction "VDD2_16") (pintype "power_in"))
      (node (ref "U6") (pin "8") (pinfunction "VCC_8") (pintype "power_in"))
    )
    (net (code "69") (name "unconnected-(H1-Pad1)") (class "Default")
      (node (ref "H1") (pin "1") (pinfunction "1_1") (pintype "passive+no_connect"))
    )
    (net (code "70") (name "unconnected-(H1-Pad15)") (class "Default")
      (node (ref "H1") (pin "15") (pinfunction "15_15") (pintype "passive+no_connect"))
    )
    (net (code "71") (name "unconnected-(H1-Pad16)") (class "Default")
      (node (ref "H1") (pin "16") (pinfunction "16_16") (pintype "passive+no_connect"))
    )
    (net (code "72") (name "unconnected-(H1-Pad17)") (class "Default")
      (node (ref "H1") (pin "17") (pinfunction "17_17") (pintype "passive+no_connect"))
    )
    (net (code "73") (name "unconnected-(H1-Pad19)") (class "Default")
      (node (ref "H1") (pin "19") (pinfunction "19_19") (pintype "passive+no_connect"))
    )
    (net (code "74") (name "unconnected-(H1-Pad21)") (class "Default")
      (node (ref "H1") (pin "21") (pinfunction "21_21") (pintype "passive+no_connect"))
    )
    (net (code "75") (name "unconnected-(H1-Pad23)") (class "Default")
      (node (ref "H1") (pin "23") (pinfunction "23_23") (pintype "passive+no_connect"))
    )
    (net (code "76") (name "unconnected-(H1-Pad24)") (class "Default")
      (node (ref "H1") (pin "24") (pinfunction "24_24") (pintype "passive+no_connect"))
    )
    (net (code "77") (name "unconnected-(H1-Pad26)") (class "Default")
      (node (ref "H1") (pin "26") (pinfunction "26_26") (pintype "passive+no_connect"))
    )
    (net (code "78") (name "unconnected-(H1-Pad29)") (class "Default")
      (node (ref "H1") (pin "29") (pinfunction "29_29") (pintype "passive+no_connect"))
    )
    (net (code "79") (name "unconnected-(H1-Pad31)") (class "Default")
      (node (ref "H1") (pin "31") (pinfunction "31_31") (pintype "passive+no_connect"))
    )
    (net (code "80") (name "unconnected-(H2-PadS)") (class "Default")
      (node (ref "H2") (pin "S") (pinfunction "S_S") (pintype "passive+no_connect"))
    )
    (net (code "81") (name "unconnected-(H3-PadS)") (class "Default")
      (node (ref "H3") (pin "S") (pinfunction "S_S") (pintype "passive+no_connect"))
    )
    (net (code "82") (name "unconnected-(H4-PadS)") (class "Default")
      (node (ref "H4") (pin "S") (pinfunction "S_S") (pintype "passive+no_connect"))
    )
    (net (code "83") (name "unconnected-(U3-OUTB-Pad7)") (class "Default")
      (node (ref "U3") (pin "7") (pinfunction "OUTB_7") (pintype "output+no_connect"))
    )
    (net (code "84") (name "unconnected-(U5-VBREF-Pad6)") (class "Default")
      (node (ref "U5") (pin "6") (pinfunction "VBREF_6") (pintype "passive+no_connect"))
    )
  )
)
